# 28_PP0_SGMII_LED_TWSI.net
KiCad netlist of a schematic drawn in Altium Designer
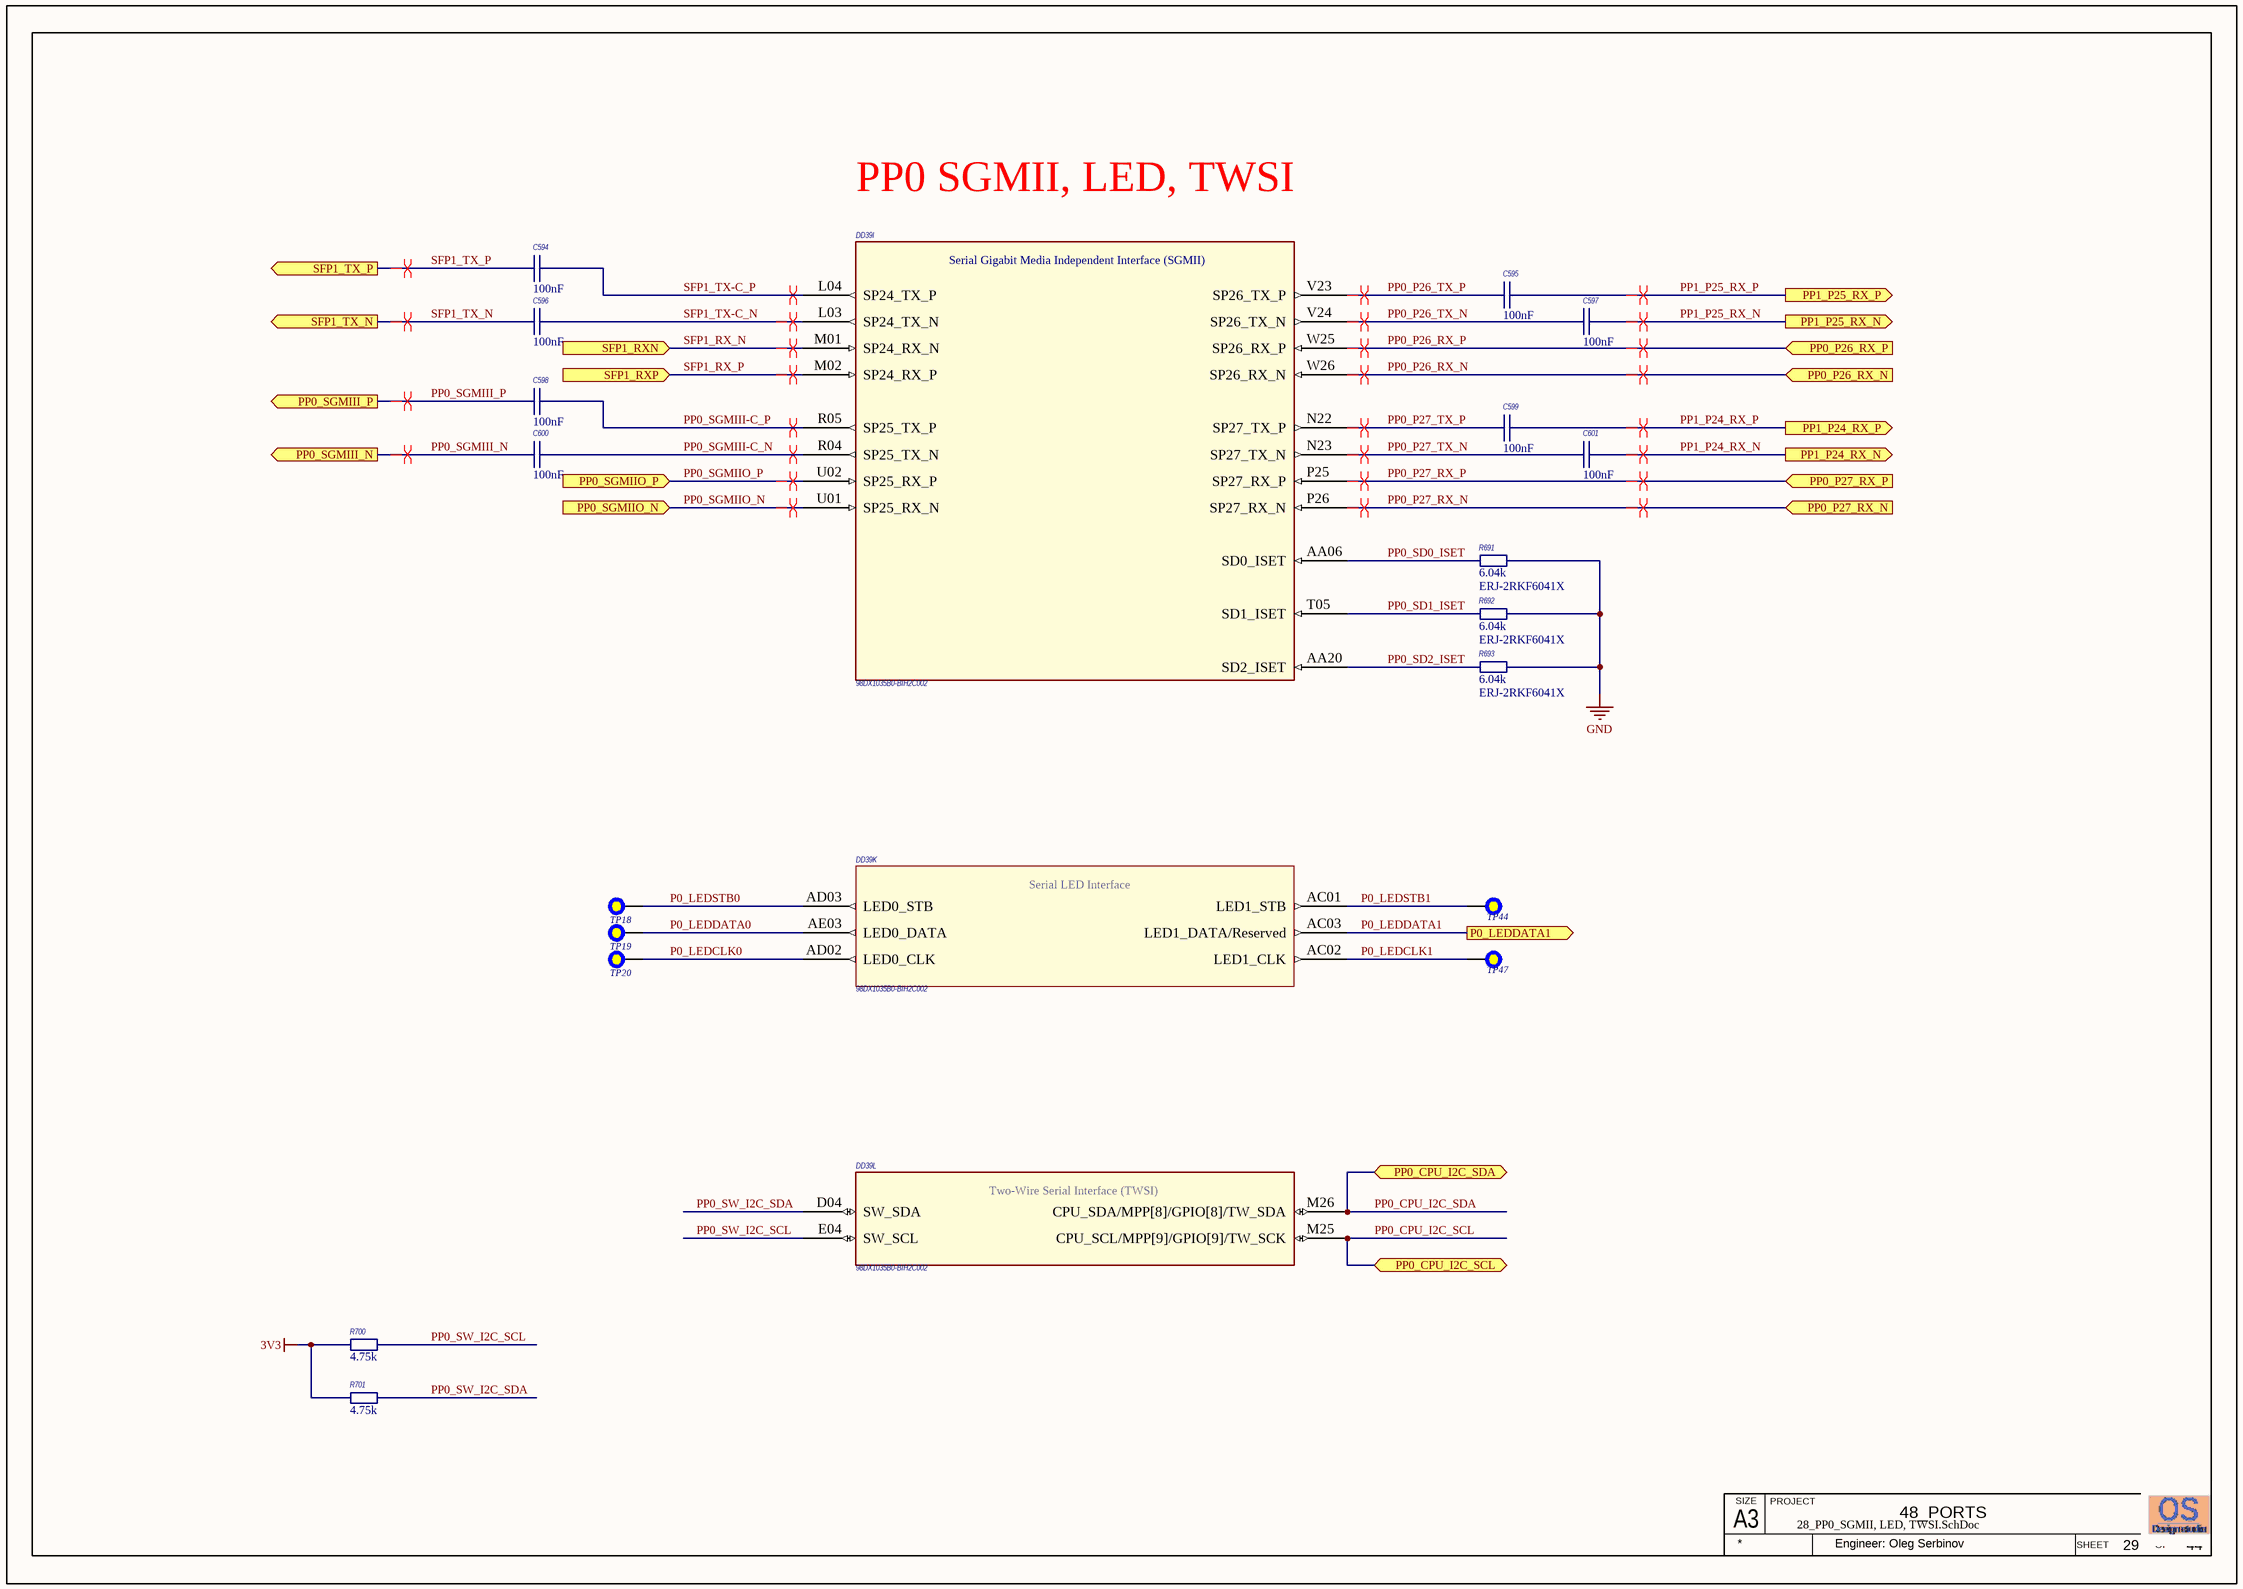
[diagram p0: 28_PP0_SGMII, LED, TWSI.SchDoc]

(export (version "E")
  (design (tool "Eeschema 10.0.6"))
  (components
    (comp (ref "C594")
      (value "GRM155R71E104KE14D")
      (footprint "C0402_IPC High Density")
      (description "C0402, 100nF, 25V, X7R")
      (fields
        (field (name "MANUFACTURER") "Murata")
        (field (name "CAPACITANCE") "100nF")
        (field (name "CUSTOMER PART NUMBER") "Конденсатор, 100n, 0402, 25V, X7R, 10%")
      )
      (libsource (lib "CAPACITORS") (part "GRM155R71E104KE14D"))
    )
    (comp (ref "C595")
      (value "GRM155R71E104KE14D")
      (footprint "C0402_IPC High Density")
      (description "C0402, 100nF, 25V, X7R")
      (fields
        (field (name "MANUFACTURER") "Murata")
        (field (name "CAPACITANCE") "100nF")
        (field (name "CUSTOMER PART NUMBER") "Конденсатор, 100n, 0402, 25V, X7R, 10%")
      )
      (libsource (lib "CAPACITORS") (part "GRM155R71E104KE14D"))
    )
    (comp (ref "C596")
      (value "GRM155R71E104KE14D")
      (footprint "C0402_IPC High Density")
      (description "C0402, 100nF, 25V, X7R")
      (fields
        (field (name "MANUFACTURER") "Murata")
        (field (name "CAPACITANCE") "100nF")
        (field (name "CUSTOMER PART NUMBER") "Конденсатор, 100n, 0402, 25V, X7R, 10%")
      )
      (libsource (lib "CAPACITORS") (part "GRM155R71E104KE14D"))
    )
    (comp (ref "C597")
      (value "GRM155R71E104KE14D")
      (footprint "C0402_IPC High Density")
      (description "C0402, 100nF, 25V, X7R")
      (fields
        (field (name "MANUFACTURER") "Murata")
        (field (name "CAPACITANCE") "100nF")
        (field (name "CUSTOMER PART NUMBER") "Конденсатор, 100n, 0402, 25V, X7R, 10%")
      )
      (libsource (lib "CAPACITORS") (part "GRM155R71E104KE14D"))
    )
    (comp (ref "C598")
      (value "GRM155R71E104KE14D")
      (footprint "C0402_IPC High Density")
      (description "C0402, 100nF, 25V, X7R")
      (fields
        (field (name "MANUFACTURER") "Murata")
        (field (name "CAPACITANCE") "100nF")
        (field (name "CUSTOMER PART NUMBER") "Конденсатор, 100n, 0402, 25V, X7R, 10%")
      )
      (libsource (lib "CAPACITORS") (part "GRM155R71E104KE14D"))
    )
    (comp (ref "C599")
      (value "GRM155R71E104KE14D")
      (footprint "C0402_IPC High Density")
      (description "C0402, 100nF, 25V, X7R")
      (fields
        (field (name "MANUFACTURER") "Murata")
        (field (name "CAPACITANCE") "100nF")
        (field (name "CUSTOMER PART NUMBER") "Конденсатор, 100n, 0402, 25V, X7R, 10%")
      )
      (libsource (lib "CAPACITORS") (part "GRM155R71E104KE14D"))
    )
    (comp (ref "C600")
      (value "GRM155R71E104KE14D")
      (footprint "C0402_IPC High Density")
      (description "C0402, 100nF, 25V, X7R")
      (fields
        (field (name "MANUFACTURER") "Murata")
        (field (name "CAPACITANCE") "100nF")
        (field (name "CUSTOMER PART NUMBER") "Конденсатор, 100n, 0402, 25V, X7R, 10%")
      )
      (libsource (lib "CAPACITORS") (part "GRM155R71E104KE14D"))
    )
    (comp (ref "C601")
      (value "GRM155R71E104KE14D")
      (footprint "C0402_IPC High Density")
      (description "C0402, 100nF, 25V, X7R")
      (fields
        (field (name "MANUFACTURER") "Murata")
        (field (name "CAPACITANCE") "100nF")
        (field (name "CUSTOMER PART NUMBER") "Конденсатор, 100n, 0402, 25V, X7R, 10%")
      )
      (libsource (lib "CAPACITORS") (part "GRM155R71E104KE14D"))
    )
    (comp (ref "DD39")
      (value "98DX1035B0-BIH2C002")
      (footprint "HSBGA617_27X27_1MM")
      (description "IC 24-PORT FE  4-PORT 2.5GE L2 ENTRY-LEVEL, CPU")
      (fields
        (field (name "CUSTOMER PART NUMBER") "Микросхема, 98DX1035B0-BIH2C002, IC 24-PORT FE 4-PORT 2.5GE L2 ENTRY-LEVEL, HSBGA617SBGA617")
        (field (name "MANUFACTURER") "Marvell Technology Group")
      )
      (libsource (lib "DIGITAL and ANALIG ICs") (part "98DX1035A1-BIH2C002"))
    )
    (comp (ref "R691")
      (value "ERJ-2RKF6041X")
      (footprint "R0402_IPC High Density")
      (description "R0402, 6.04k 1%")
      (fields
        (field (name "TOLERANCE") "±1%")
        (field (name "MANUFACTURER") "Panasonic")
        (field (name "RESISTANCE (OHMS)") "6.04k")
        (field (name "MANUFACTURER PART NUMBER") "ERJ-2RKF6041X")
      )
      (libsource (lib "RESISTOR") (part "ERJ-2RKF6041X"))
    )
    (comp (ref "R692")
      (value "ERJ-2RKF6041X")
      (footprint "R0402_IPC High Density")
      (description "R0402, 6.04k 1%")
      (fields
        (field (name "TOLERANCE") "±1%")
        (field (name "MANUFACTURER") "Panasonic")
        (field (name "RESISTANCE (OHMS)") "6.04k")
        (field (name "MANUFACTURER PART NUMBER") "ERJ-2RKF6041X")
      )
      (libsource (lib "RESISTOR") (part "ERJ-2RKF6041X"))
    )
    (comp (ref "R693")
      (value "ERJ-2RKF6041X")
      (footprint "R0402_IPC High Density")
      (description "R0402, 6.04k 1%")
      (fields
        (field (name "TOLERANCE") "±1%")
        (field (name "MANUFACTURER") "Panasonic")
        (field (name "RESISTANCE (OHMS)") "6.04k")
        (field (name "MANUFACTURER PART NUMBER") "ERJ-2RKF6041X")
      )
      (libsource (lib "RESISTOR") (part "ERJ-2RKF6041X"))
    )
    (comp (ref "R700")
      (value "ERJ-2RKF4751X")
      (footprint "R0402_IPC High Density")
      (description "R0402, 4.75k 1%")
      (fields
        (field (name "TOLERANCE") "±1%")
        (field (name "MANUFACTURER") "Panasonic")
        (field (name "RESISTANCE (OHMS)") "4.75k")
      )
      (libsource (lib "RESISTOR") (part "ERJ-2RKF4751X"))
    )
    (comp (ref "R701")
      (value "ERJ-2RKF4751X")
      (footprint "R0402_IPC High Density")
      (description "R0402, 4.75k 1%")
      (fields
        (field (name "TOLERANCE") "±1%")
        (field (name "MANUFACTURER") "Panasonic")
        (field (name "RESISTANCE (OHMS)") "4.75k")
      )
      (libsource (lib "RESISTOR") (part "ERJ-2RKF4751X"))
    )
    (comp (ref "TP18")
      (value "Test Point 0.5mm pad")
      (footprint "Test Point 0.5mm")
      (libsource (lib "CONNECTORS") (part "Test Point 0.5mm pad"))
    )
    (comp (ref "TP19")
      (value "Test Point 0.5mm pad")
      (footprint "Test Point 0.5mm")
      (libsource (lib "CONNECTORS") (part "Test Point 0.5mm pad"))
    )
    (comp (ref "TP20")
      (value "Test Point 0.5mm pad")
      (footprint "Test Point 0.5mm")
      (libsource (lib "CONNECTORS") (part "Test Point 0.5mm pad"))
    )
    (comp (ref "TP44")
      (value "Test Point 0.5mm pad")
      (footprint "Test Point 0.5mm")
      (libsource (lib "CONNECTORS") (part "Test Point 0.5mm pad"))
    )
    (comp (ref "TP47")
      (value "Test Point 0.5mm pad")
      (footprint "Test Point 0.5mm")
      (libsource (lib "CONNECTORS") (part "Test Point 0.5mm pad"))
    )
  )
  (nets
    (net (code "1") (name "/P0_LEDCLK0") (class "Default")
      (node (ref "DD39") (pin "AD02") (pinfunction "LED0_CLK_AD02") (pintype "output"))
      (node (ref "TP20") (pin "1") (pinfunction "1_1") (pintype "passive"))
    )
    (net (code "2") (name "/P0_LEDCLK1") (class "Default")
      (node (ref "DD39") (pin "AC02") (pinfunction "LED1_CLK_AC02") (pintype "output"))
      (node (ref "TP47") (pin "1") (pinfunction "1_1") (pintype "passive"))
    )
    (net (code "3") (name "/P0_LEDDATA0") (class "Default")
      (node (ref "DD39") (pin "AE03") (pinfunction "LED0_DATA_AE03") (pintype "output"))
      (node (ref "TP19") (pin "1") (pinfunction "1_1") (pintype "passive"))
    )
    (net (code "4") (name "/P0_LEDDATA1") (class "Default")
      (node (ref "DD39") (pin "AC03") (pinfunction "LED1_DATA/Reserved_AC03") (pintype "output"))
    )
    (net (code "5") (name "/P0_LEDSTB0") (class "Default")
      (node (ref "DD39") (pin "AD03") (pinfunction "LED0_STB_AD03") (pintype "output"))
      (node (ref "TP18") (pin "1") (pinfunction "1_1") (pintype "passive"))
    )
    (net (code "6") (name "/P0_LEDSTB1") (class "Default")
      (node (ref "DD39") (pin "AC01") (pinfunction "LED1_STB_AC01") (pintype "output"))
      (node (ref "TP44") (pin "1") (pinfunction "1_1") (pintype "passive"))
    )
    (net (code "7") (name "/PP0_CPU_I2C_SCL") (class "Default")
      (node (ref "DD39") (pin "M25") (pinfunction "CPU_SCL/MPP[9]/GPIO[9]/TW_SCK_M25") (pintype "bidirectional"))
    )
    (net (code "8") (name "/PP0_CPU_I2C_SDA") (class "Default")
      (node (ref "DD39") (pin "M26") (pinfunction "CPU_SDA/MPP[8]/GPIO[8]/TW_SDA_M26") (pintype "bidirectional"))
    )
    (net (code "9") (name "/PP0_P26_RX_N") (class "Default")
      (node (ref "DD39") (pin "W26") (pinfunction "SP26_RX_N_W26") (pintype "input"))
    )
    (net (code "10") (name "/PP0_P26_RX_P") (class "Default")
      (node (ref "DD39") (pin "W25") (pinfunction "SP26_RX_P_W25") (pintype "input"))
    )
    (net (code "11") (name "/PP0_P26_TX_N") (class "Default")
      (node (ref "C597") (pin "2") (pintype "passive"))
      (node (ref "DD39") (pin "V24") (pinfunction "SP26_TX_N_V24") (pintype "output"))
    )
    (net (code "12") (name "/PP0_P26_TX_P") (class "Default")
      (node (ref "C595") (pin "2") (pintype "passive"))
      (node (ref "DD39") (pin "V23") (pinfunction "SP26_TX_P_V23") (pintype "output"))
    )
    (net (code "13") (name "/PP0_P27_RX_N") (class "Default")
      (node (ref "DD39") (pin "P26") (pinfunction "SP27_RX_N_P26") (pintype "input"))
    )
    (net (code "14") (name "/PP0_P27_RX_P") (class "Default")
      (node (ref "DD39") (pin "P25") (pinfunction "SP27_RX_P_P25") (pintype "input"))
    )
    (net (code "15") (name "/PP0_P27_TX_N") (class "Default")
      (node (ref "C601") (pin "2") (pintype "passive"))
      (node (ref "DD39") (pin "N23") (pinfunction "SP27_TX_N_N23") (pintype "output"))
    )
    (net (code "16") (name "/PP0_P27_TX_P") (class "Default")
      (node (ref "C599") (pin "2") (pintype "passive"))
      (node (ref "DD39") (pin "N22") (pinfunction "SP27_TX_P_N22") (pintype "output"))
    )
    (net (code "17") (name "/PP0_SD0_ISET") (class "Default")
      (node (ref "DD39") (pin "AA06") (pinfunction "SD0_ISET_AA06") (pintype "input"))
      (node (ref "R691") (pin "1") (pintype "passive"))
    )
    (net (code "18") (name "/PP0_SD1_ISET") (class "Default")
      (node (ref "DD39") (pin "T05") (pinfunction "SD1_ISET_T05") (pintype "input"))
      (node (ref "R692") (pin "1") (pintype "passive"))
    )
    (net (code "19") (name "/PP0_SD2_ISET") (class "Default")
      (node (ref "DD39") (pin "AA20") (pinfunction "SD2_ISET_AA20") (pintype "input"))
      (node (ref "R693") (pin "1") (pintype "passive"))
    )
    (net (code "20") (name "/PP0_SGMIII-С_N") (class "Default")
      (node (ref "C600") (pin "1") (pintype "passive"))
      (node (ref "DD39") (pin "R04") (pinfunction "SP25_TX_N_R04") (pintype "output"))
    )
    (net (code "21") (name "/PP0_SGMIII-С_P") (class "Default")
      (node (ref "C598") (pin "1") (pintype "passive"))
      (node (ref "DD39") (pin "R05") (pinfunction "SP25_TX_P_R05") (pintype "output"))
    )
    (net (code "22") (name "/PP0_SGMIII_N") (class "Default")
      (node (ref "C600") (pin "2") (pintype "passive"))
    )
    (net (code "23") (name "/PP0_SGMIII_P") (class "Default")
      (node (ref "C598") (pin "2") (pintype "passive"))
    )
    (net (code "24") (name "/PP0_SGMIIO_N") (class "Default")
      (node (ref "DD39") (pin "U01") (pinfunction "SP25_RX_N_U01") (pintype "input"))
    )
    (net (code "25") (name "/PP0_SGMIIO_P") (class "Default")
      (node (ref "DD39") (pin "U02") (pinfunction "SP25_RX_P_U02") (pintype "input"))
    )
    (net (code "26") (name "/PP0_SW_I2C_SCL") (class "Default")
      (node (ref "DD39") (pin "E04") (pinfunction "SW_SCL_E04") (pintype "bidirectional"))
      (node (ref "R700") (pin "2") (pintype "passive"))
    )
    (net (code "27") (name "/PP0_SW_I2C_SDA") (class "Default")
      (node (ref "DD39") (pin "D04") (pinfunction "SW_SDA_D04") (pintype "bidirectional"))
      (node (ref "R701") (pin "2") (pintype "passive"))
    )
    (net (code "28") (name "/PP1_P24_RX_N") (class "Default")
      (node (ref "C601") (pin "1") (pintype "passive"))
    )
    (net (code "29") (name "/PP1_P24_RX_P") (class "Default")
      (node (ref "C599") (pin "1") (pintype "passive"))
    )
    (net (code "30") (name "/PP1_P25_RX_N") (class "Default")
      (node (ref "C597") (pin "1") (pintype "passive"))
    )
    (net (code "31") (name "/PP1_P25_RX_P") (class "Default")
      (node (ref "C595") (pin "1") (pintype "passive"))
    )
    (net (code "32") (name "/SFP1_RX_N") (class "Default")
      (node (ref "DD39") (pin "M01") (pinfunction "SP24_RX_N_M01") (pintype "input"))
    )
    (net (code "33") (name "/SFP1_RX_P") (class "Default")
      (node (ref "DD39") (pin "M02") (pinfunction "SP24_RX_P_M02") (pintype "input"))
    )
    (net (code "34") (name "/SFP1_TX-С_N") (class "Default")
      (node (ref "C596") (pin "1") (pintype "passive"))
      (node (ref "DD39") (pin "L03") (pinfunction "SP24_TX_N_L03") (pintype "output"))
    )
    (net (code "35") (name "/SFP1_TX-С_P") (class "Default")
      (node (ref "C594") (pin "1") (pintype "passive"))
      (node (ref "DD39") (pin "L04") (pinfunction "SP24_TX_P_L04") (pintype "output"))
    )
    (net (code "36") (name "/SFP1_TX_N") (class "Default") (node (ref "C596") (pin "2") (pintype "passive")))
    (net (code "37") (name "/SFP1_TX_P") (class "Default") (node (ref "C594") (pin "2") (pintype "passive")))
    (net (code "38") (name "3V3") (class "Default")
      (node (ref "R700") (pin "1") (pintype "passive"))
      (node (ref "R701") (pin "1") (pintype "passive"))
    )
    (net (code "39") (name "GND") (class "Default")
      (node (ref "R691") (pin "2") (pintype "passive"))
      (node (ref "R692") (pin "2") (pintype "passive"))
      (node (ref "R693") (pin "2") (pintype "passive"))
    )
  )
)
